# Sheet1.net
KiCad netlist of a schematic drawn in Altium Designer
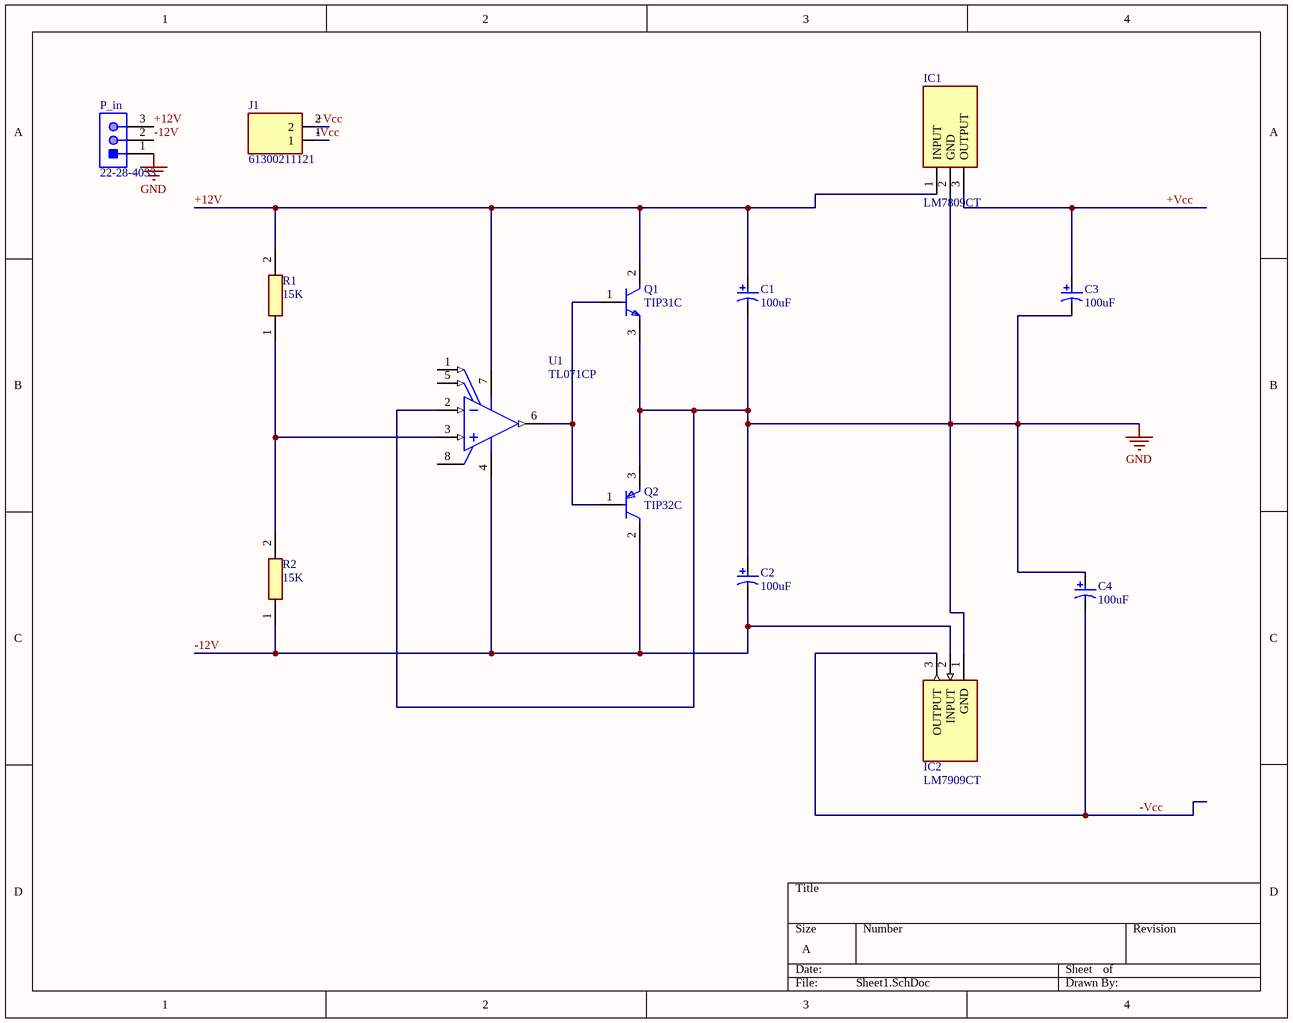
[diagram p0: Sheet1.SchDoc]

(export (version "E")
  (design (tool "Eeschema 10.0.6"))
  (components
    (comp (ref "C1")
      (value "100uF")
      (footprint "CAPPR65-350-1150X800X1250")
      (description "Aluminum Electrolytic Capacitor, 100 uF, +/- 20%, 50 V, -40 to 85 degC, 2-Pin THD, RoHS, Bulk")
      (fields (field (name "MANUFACTURER") "Panasonic") (field (name "VOLTAGE") "50V"))
      (libsource (lib "Altium Content Vault") (part "CAP-P-2"))
    )
    (comp (ref "C2")
      (value "100uF")
      (footprint "CAPPR65-350-1150X800X1250")
      (description "Aluminum Electrolytic Capacitor, 100 uF, +/- 20%, 50 V, -40 to 85 degC, 2-Pin THD, RoHS, Bulk")
      (fields (field (name "MANUFACTURER") "Panasonic") (field (name "VOLTAGE") "50V"))
      (libsource (lib "Altium Content Vault") (part "CAP-P-2"))
    )
    (comp (ref "C3")
      (value "100uF")
      (footprint "CAPPR65-350-1150X800X1250")
      (description "Aluminum Electrolytic Capacitor, 100 uF, +/- 20%, 50 V, -40 to 85 degC, 2-Pin THD, RoHS, Bulk")
      (fields (field (name "MANUFACTURER") "Panasonic") (field (name "VOLTAGE") "50V"))
      (libsource (lib "Altium Content Vault") (part "CAP-P-2"))
    )
    (comp (ref "C4")
      (value "100uF")
      (footprint "CAPPR65-350-1150X800X1250")
      (description "Aluminum Electrolytic Capacitor, 100 uF, +/- 20%, 50 V, -40 to 85 degC, 2-Pin THD, RoHS, Bulk")
      (fields (field (name "MANUFACTURER") "Panasonic") (field (name "VOLTAGE") "50V"))
      (libsource (lib "Altium Content Vault") (part "CAP-P-2"))
    )
    (comp (ref "IC1")
      (value "LM7809CT")
      (footprint "SamacSys:TO254P470X1016X2019-3P")
      (description "Power Supply")
      (fields (field (name "MOUSER PART NUMBER") "512-LM7809CT"))
      (libsource (lib "*") (part "LM7809CT"))
    )
    (comp (ref "IC2")
      (value "LM7909CT")
      (footprint "SamacSys:TO254P483X1016X2261-3P")
      (description "Integrated Circuit")
      (fields (field (name "MOUSER PART NUMBER") "512-LM7909CT"))
      (libsource (lib "*") (part "LM7909CT"))
    )
    (comp (ref "J1")
      (value "61300211121")
      (footprint "SamacSys:HDRV2W110P0X254_1X2_508X254X854P")
      (description "Connector")
      (fields (field (name "MOUSER PART NUMBER") "710-61300211121"))
      (libsource (lib "*") (part "61300211121"))
    )
    (comp (ref "P_in")
      (value "22-28-4033")
      (footprint "MOLX-22-28-4033_V")
      (description "Male Header, Pitch 2.54 mm, 1 x 3 Position, Height 8.38 mm, Tail Length 3.18 mm, RoHS, Bulk")
      (fields (field (name "MANUFACTURER") "Molex"))
      (libsource (lib "Altium Content Vault") (part "CN-1P-M-R3"))
    )
    (comp (ref "Q1")
      (value "TIP31C")
      (footprint "FP-TO-220-P0A0015988-MFG")
      (description "TRANS NPN 100V 3A TO-220")
      (fields
        (field (name "OCTOPART") "https://octopart.com/tip31c-stmicroelectronics-15555")
        (field (name "MANUFACTURER") "STMicroelectronics")
      )
      (libsource (lib "Altium Content Vault") (part "1c57d9dae74fe2702546667b0e849db"))
    )
    (comp (ref "Q2")
      (value "TIP32C")
      (footprint "FP-TO-220-P0A0015988-MFG")
      (description "TRANS PNP 100V 3A TO-220")
      (fields
        (field (name "MANUFACTURER") "STMicroelectronics")
        (field (name "OCTOPART") "https://octopart.com/tip32c-stmicroelectronics-353617")
      )
      (libsource (lib "Altium Content Vault") (part "802a31d42ca070764d097f06bc9597f"))
    )
    (comp (ref "R1")
      (value "15K")
      (footprint "SamacSys:RESAD1590W60L630D240")
      (description "Resistor")
      (fields
        (field (name "MANUFACTURER_PART_NUMBER") "CFR-25JB-52-15K")
        (field (name "MOUSER PART NUMBER") "603-CFR-25JB-52-15K")
      )
      (libsource (lib "*") (part "CFR-25JB-52-15K"))
    )
    (comp (ref "R2")
      (value "15K")
      (footprint "SamacSys:RESAD1590W60L630D240")
      (description "Resistor")
      (fields
        (field (name "MANUFACTURER_PART_NUMBER") "CFR-25JB-52-15K")
        (field (name "MOUSER PART NUMBER") "603-CFR-25JB-52-15K")
      )
      (libsource (lib "*") (part "CFR-25JB-52-15K"))
    )
    (comp (ref "U1")
      (value "TL071CP")
      (footprint "P0008A")
      (fields (field (name "MANUFACTURER") "Texas Instruments"))
      (libsource (lib "Altium Content Vault") (part "TI-AMP-S5-2-8"))
    )
  )
  (nets
    (net (code "1") (name "/+12V") (class "Default")
      (node (ref "C1") (pin "1") (pinfunction "1_1") (pintype "passive"))
      (node (ref "IC1") (pin "1") (pinfunction "INPUT_1") (pintype "passive"))
      (node (ref "P_in") (pin "3") (pinfunction "3_3") (pintype "passive"))
      (node (ref "Q1") (pin "2") (pinfunction "C_2") (pintype "passive"))
      (node (ref "R1") (pin "2") (pinfunction "2_2") (pintype "passive"))
      (node (ref "U1") (pin "7") (pinfunction "VCC+_7") (pintype "power_in"))
    )
    (net (code "2") (name "/+Vcc") (class "Default")
      (node (ref "C3") (pin "1") (pinfunction "1_1") (pintype "passive"))
      (node (ref "IC1") (pin "3") (pinfunction "OUTPUT_3") (pintype "passive"))
      (node (ref "J1") (pin "2") (pinfunction "2_2") (pintype "passive"))
    )
    (net (code "3") (name "/-12V") (class "Default")
      (node (ref "C2") (pin "2") (pinfunction "2_2") (pintype "passive"))
      (node (ref "IC2") (pin "2") (pinfunction "INPUT_2") (pintype "input"))
      (node (ref "P_in") (pin "2") (pinfunction "2_2") (pintype "passive"))
      (node (ref "Q2") (pin "2") (pinfunction "C_2") (pintype "passive"))
      (node (ref "R2") (pin "1") (pinfunction "1_1") (pintype "passive"))
      (node (ref "U1") (pin "4") (pinfunction "VCC-_4") (pintype "power_in"))
    )
    (net (code "4") (name "/-Vcc") (class "Default")
      (node (ref "C4") (pin "2") (pinfunction "2_2") (pintype "passive"))
      (node (ref "IC2") (pin "3") (pinfunction "OUTPUT_3") (pintype "output"))
      (node (ref "J1") (pin "1") (pinfunction "1_1") (pintype "passive"))
    )
    (net (code "5") (name "GND") (class "Default")
      (node (ref "C1") (pin "2") (pinfunction "2_2") (pintype "passive"))
      (node (ref "C2") (pin "1") (pinfunction "1_1") (pintype "passive"))
      (node (ref "C3") (pin "2") (pinfunction "2_2") (pintype "passive"))
      (node (ref "C4") (pin "1") (pinfunction "1_1") (pintype "passive"))
      (node (ref "IC1") (pin "2") (pinfunction "GND_2") (pintype "passive"))
      (node (ref "IC2") (pin "1") (pinfunction "GND_1") (pintype "power_in"))
      (node (ref "P_in") (pin "1") (pinfunction "1_1") (pintype "passive"))
      (node (ref "Q1") (pin "3") (pinfunction "E_3") (pintype "passive"))
      (node (ref "Q2") (pin "3") (pinfunction "E_3") (pintype "passive"))
      (node (ref "U1") (pin "2") (pinfunction "IN-_2") (pintype "input"))
    )
    (net (code "6") (name "Net-(Q1-B)") (class "Default")
      (node (ref "Q1") (pin "1") (pinfunction "B_1") (pintype "passive"))
      (node (ref "Q2") (pin "1") (pinfunction "B_1") (pintype "passive"))
      (node (ref "U1") (pin "6") (pinfunction "OUT_6") (pintype "output"))
    )
    (net (code "7") (name "Net-(U1-IN+)") (class "Default")
      (node (ref "R1") (pin "1") (pinfunction "1_1") (pintype "passive"))
      (node (ref "R2") (pin "2") (pinfunction "2_2") (pintype "passive"))
      (node (ref "U1") (pin "3") (pinfunction "IN+_3") (pintype "input"))
    )
    (net (code "8") (name "unconnected-(U1-NC-Pad8)") (class "Default")
      (node (ref "U1") (pin "8") (pinfunction "NC_8") (pintype "passive"))
    )
    (net (code "9") (name "unconnected-(U1-OFFSET_N1-Pad1)") (class "Default")
      (node (ref "U1") (pin "1") (pinfunction "OFFSET_N1_1") (pintype "input"))
    )
    (net (code "10") (name "unconnected-(U1-OFFSET_N2-Pad5)") (class "Default")
      (node (ref "U1") (pin "5") (pinfunction "OFFSET_N2_5") (pintype "input"))
    )
  )
)
